# OUT_Connectors.net
KiCad netlist of a schematic drawn in Altium Designer
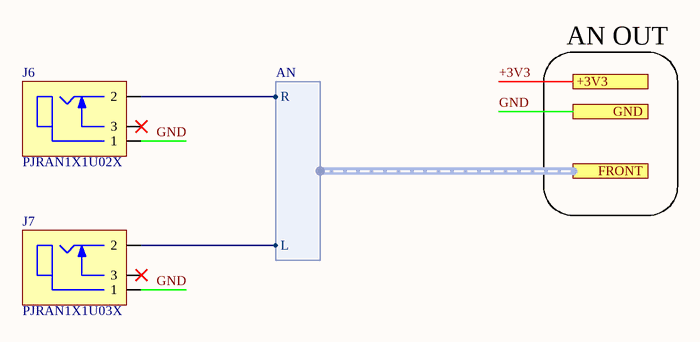
[diagram p0: OUT_Connectors.SchDoc]

(export (version "E")
  (design (tool "Eeschema 10.0.6"))
  (components
    (comp (ref "J6")
      (value "PJRAN1X1U02X")
      (footprint "RCA1X1-RA - SW")
      (description "CONN RCA JACK MONO 3.2MM R/A WHITE")
      (libsource (lib "LIB2022 - Connectors") (part "PJRAN1X1U02X"))
    )
    (comp (ref "J7")
      (value "PJRAN1X1U03X")
      (footprint "RCA1X1-RA - SW")
      (description "CONN RCA JACK MONO 3.2MM R/A RED")
      (libsource (lib "LIB2022 - Connectors") (part "PJRAN1X1U03X"))
    )
  )
  (nets
    (net (code "3") (name "/GND") (class "Default")
      (node (ref "J6") (pin "1") (pinfunction "1_1") (pintype "passive"))
      (node (ref "J7") (pin "1") (pinfunction "1_1") (pintype "passive"))
    )
    (net (code "4") (name "/L") (class "Default")
      (node (ref "J7") (pin "2") (pinfunction "2_2") (pintype "passive"))
    )
    (net (code "5") (name "/R") (class "Default")
      (node (ref "J6") (pin "2") (pinfunction "2_2") (pintype "passive"))
    )
    (net (code "7") (name "unconnected-(J6-Pad3)") (class "Default")
      (node (ref "J6") (pin "3") (pinfunction "3_3") (pintype "passive+no_connect"))
    )
    (net (code "8") (name "unconnected-(J7-Pad3)") (class "Default")
      (node (ref "J7") (pin "3") (pinfunction "3_3") (pintype "passive+no_connect"))
    )
  )
)
